# Z05_C8V_01.net
KiCad netlist of a schematic drawn in EAGLE
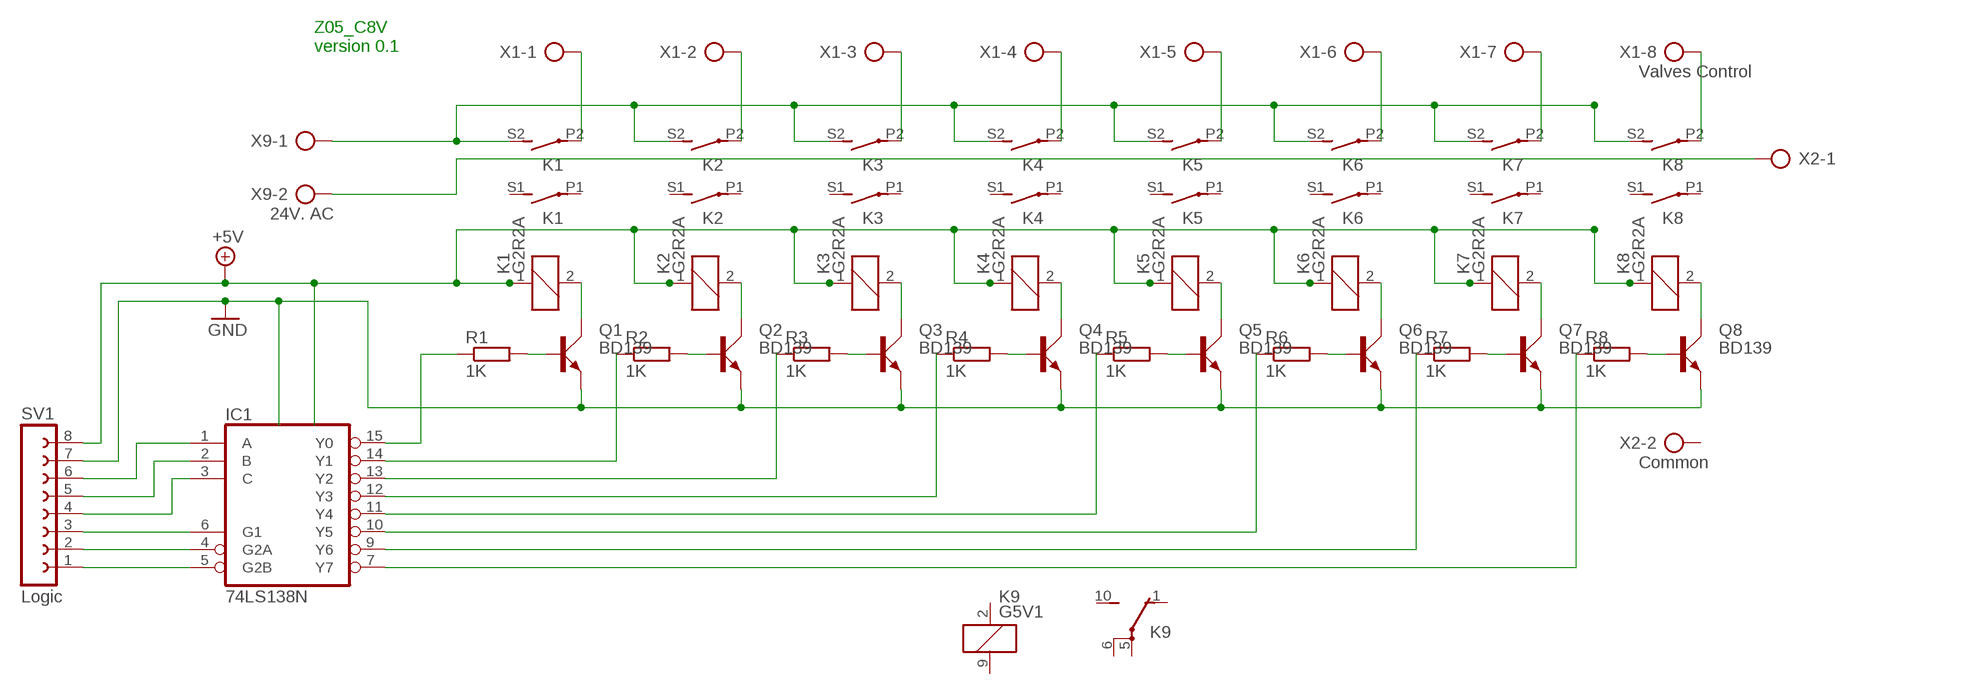
[diagram p0: schematic, sheet 1]

(export (version "E")
  (design (tool "Eeschema 10.0.6"))
  (components
    (comp (ref "IC1")
      (value "74LS138N")
      (footprint "eagle-import:DIL16")
      (libsource (lib "eagle-import") (part "74138NLS"))
    )
    (comp (ref "K1")
      (value "G2R2A")
      (footprint "eagle-import:G2R2A")
      (fields (field (name "MPN") "G2R-2A-DC24"))
      (libsource (lib "eagle-import") (part "G2R2A"))
    )
    (comp (ref "K2")
      (value "G2R2A")
      (footprint "eagle-import:G2R2A")
      (fields (field (name "MPN") "G2R-2A-DC24"))
      (libsource (lib "eagle-import") (part "G2R2A"))
    )
    (comp (ref "K3")
      (value "G2R2A")
      (footprint "eagle-import:G2R2A")
      (fields (field (name "MPN") "G2R-2A-DC24"))
      (libsource (lib "eagle-import") (part "G2R2A"))
    )
    (comp (ref "K4")
      (value "G2R2A")
      (footprint "eagle-import:G2R2A")
      (fields (field (name "MPN") "G2R-2A-DC24"))
      (libsource (lib "eagle-import") (part "G2R2A"))
    )
    (comp (ref "K5")
      (value "G2R2A")
      (footprint "eagle-import:G2R2A")
      (fields (field (name "MPN") "G2R-2A-DC24"))
      (libsource (lib "eagle-import") (part "G2R2A"))
    )
    (comp (ref "K6")
      (value "G2R2A")
      (footprint "eagle-import:G2R2A")
      (fields (field (name "MPN") "G2R-2A-DC24"))
      (libsource (lib "eagle-import") (part "G2R2A"))
    )
    (comp (ref "K7")
      (value "G2R2A")
      (footprint "eagle-import:G2R2A")
      (fields (field (name "MPN") "G2R-2A-DC24"))
      (libsource (lib "eagle-import") (part "G2R2A"))
    )
    (comp (ref "K8")
      (value "G2R2A")
      (footprint "eagle-import:G2R2A")
      (fields (field (name "MPN") "G2R-2A-DC24"))
      (libsource (lib "eagle-import") (part "G2R2A"))
    )
    (comp (ref "K9")
      (value "G5V1")
      (footprint "eagle-import:G5V1")
      (fields (field (name "MPN") "G5V-1-DC24"))
      (libsource (lib "eagle-import") (part "G5V1"))
    )
    (comp (ref "Q1")
      (value "BD139")
      (footprint "eagle-import:TO126AV")
      (libsource (lib "eagle-import") (part "BD139"))
    )
    (comp (ref "Q2")
      (value "BD139")
      (footprint "eagle-import:TO126AV")
      (libsource (lib "eagle-import") (part "BD139"))
    )
    (comp (ref "Q3")
      (value "BD139")
      (footprint "eagle-import:TO126AV")
      (libsource (lib "eagle-import") (part "BD139"))
    )
    (comp (ref "Q4")
      (value "BD139")
      (footprint "eagle-import:TO126AV")
      (libsource (lib "eagle-import") (part "BD139"))
    )
    (comp (ref "Q5")
      (value "BD139")
      (footprint "eagle-import:TO126AV")
      (libsource (lib "eagle-import") (part "BD139"))
    )
    (comp (ref "Q6")
      (value "BD139")
      (footprint "eagle-import:TO126AV")
      (libsource (lib "eagle-import") (part "BD139"))
    )
    (comp (ref "Q7")
      (value "BD139")
      (footprint "eagle-import:TO126AV")
      (libsource (lib "eagle-import") (part "BD139"))
    )
    (comp (ref "Q8")
      (value "BD139")
      (footprint "eagle-import:TO126AV")
      (libsource (lib "eagle-import") (part "BD139"))
    )
    (comp (ref "R1")
      (value "1K")
      (footprint "eagle-import:0204_7")
      (libsource (lib "eagle-import") (part "R-EU_0204/7"))
    )
    (comp (ref "R2")
      (value "1K")
      (footprint "eagle-import:0204_7")
      (libsource (lib "eagle-import") (part "R-EU_0204/7"))
    )
    (comp (ref "R3")
      (value "1K")
      (footprint "eagle-import:0204_7")
      (libsource (lib "eagle-import") (part "R-EU_0204/7"))
    )
    (comp (ref "R4")
      (value "1K")
      (footprint "eagle-import:0204_7")
      (libsource (lib "eagle-import") (part "R-EU_0204/7"))
    )
    (comp (ref "R5")
      (value "1K")
      (footprint "eagle-import:0204_7")
      (libsource (lib "eagle-import") (part "R-EU_0204/7"))
    )
    (comp (ref "R6")
      (value "1K")
      (footprint "eagle-import:0204_7")
      (libsource (lib "eagle-import") (part "R-EU_0204/7"))
    )
    (comp (ref "R7")
      (value "1K")
      (footprint "eagle-import:0204_7")
      (libsource (lib "eagle-import") (part "R-EU_0204/7"))
    )
    (comp (ref "R8")
      (value "1K")
      (footprint "eagle-import:0204_7")
      (libsource (lib "eagle-import") (part "R-EU_0204/7"))
    )
    (comp (ref "SV1")
      (value "Logic")
      (footprint "eagle-import:FE08")
      (libsource (lib "eagle-import") (part "FE08-1"))
    )
    (comp (ref "X1")
      (value "Valves Control")
      (footprint "eagle-import:AK300_8")
      (libsource (lib "eagle-import") (part "AK300/8"))
    )
    (comp (ref "X2")
      (value "Common")
      (footprint "eagle-import:AK300_2")
      (libsource (lib "eagle-import") (part "AK300/2"))
    )
    (comp (ref "X9")
      (value "24V. AC")
      (footprint "eagle-import:AK300_2")
      (libsource (lib "eagle-import") (part "AK300/2"))
    )
  )
  (nets
    (net (code "1") (name "+5V") (class "Default")
      (node (ref "K1") (pin "1") (pinfunction "1_1") (pintype "passive"))
      (node (ref "K2") (pin "1") (pinfunction "1_1") (pintype "passive"))
      (node (ref "K3") (pin "1") (pinfunction "1_1") (pintype "passive"))
      (node (ref "K4") (pin "1") (pinfunction "1_1") (pintype "passive"))
      (node (ref "K5") (pin "1") (pinfunction "1_1") (pintype "passive"))
      (node (ref "K6") (pin "1") (pinfunction "1_1") (pintype "passive"))
      (node (ref "K7") (pin "1") (pinfunction "1_1") (pintype "passive"))
      (node (ref "K8") (pin "1") (pinfunction "1_1") (pintype "passive"))
      (node (ref "SV1") (pin "8") (pinfunction "8_8") (pintype "passive"))
    )
    (net (code "2") (name "GND") (class "Default")
      (node (ref "Q1") (pin "E") (pinfunction "E_E") (pintype "passive"))
      (node (ref "Q2") (pin "E") (pinfunction "E_E") (pintype "passive"))
      (node (ref "Q3") (pin "E") (pinfunction "E_E") (pintype "passive"))
      (node (ref "Q4") (pin "E") (pinfunction "E_E") (pintype "passive"))
      (node (ref "Q5") (pin "E") (pinfunction "E_E") (pintype "passive"))
      (node (ref "Q6") (pin "E") (pinfunction "E_E") (pintype "passive"))
      (node (ref "Q7") (pin "E") (pinfunction "E_E") (pintype "passive"))
      (node (ref "Q8") (pin "E") (pinfunction "E_E") (pintype "passive"))
      (node (ref "SV1") (pin "7") (pinfunction "7_7") (pintype "passive"))
    )
    (net (code "3") (name "Net-(IC1A-A)") (class "Default")
      (node (ref "IC1") (pin "1") (pinfunction "A_1") (pintype "input"))
      (node (ref "SV1") (pin "6") (pinfunction "6_6") (pintype "passive"))
    )
    (net (code "4") (name "Net-(IC1A-B)") (class "Default")
      (node (ref "IC1") (pin "2") (pinfunction "B_2") (pintype "input"))
      (node (ref "SV1") (pin "5") (pinfunction "5_5") (pintype "passive"))
    )
    (net (code "5") (name "Net-(IC1A-C)") (class "Default")
      (node (ref "IC1") (pin "3") (pinfunction "C_3") (pintype "input"))
      (node (ref "SV1") (pin "4") (pinfunction "4_4") (pintype "passive"))
    )
    (net (code "6") (name "Net-(IC1A-G1)") (class "Default")
      (node (ref "IC1") (pin "6") (pinfunction "G1_6") (pintype "input"))
      (node (ref "SV1") (pin "3") (pinfunction "3_3") (pintype "passive"))
    )
    (net (code "7") (name "Net-(IC1A-G2A)") (class "Default")
      (node (ref "IC1") (pin "4") (pinfunction "G2A_4") (pintype "input"))
      (node (ref "SV1") (pin "2") (pinfunction "2_2") (pintype "passive"))
    )
    (net (code "8") (name "Net-(IC1A-G2B)") (class "Default")
      (node (ref "IC1") (pin "5") (pinfunction "G2B_5") (pintype "input"))
      (node (ref "SV1") (pin "1") (pinfunction "1_1") (pintype "passive"))
    )
    (net (code "9") (name "Net-(IC1A-Y0)") (class "Default")
      (node (ref "IC1") (pin "15") (pinfunction "Y0_15") (pintype "output"))
      (node (ref "R1") (pin "1") (pinfunction "1_1") (pintype "passive"))
    )
    (net (code "10") (name "Net-(IC1A-Y1)") (class "Default")
      (node (ref "IC1") (pin "14") (pinfunction "Y1_14") (pintype "output"))
      (node (ref "R2") (pin "1") (pinfunction "1_1") (pintype "passive"))
    )
    (net (code "11") (name "Net-(IC1A-Y2)") (class "Default")
      (node (ref "IC1") (pin "13") (pinfunction "Y2_13") (pintype "output"))
      (node (ref "R3") (pin "1") (pinfunction "1_1") (pintype "passive"))
    )
    (net (code "12") (name "Net-(IC1A-Y3)") (class "Default")
      (node (ref "IC1") (pin "12") (pinfunction "Y3_12") (pintype "output"))
      (node (ref "R4") (pin "1") (pinfunction "1_1") (pintype "passive"))
    )
    (net (code "13") (name "Net-(IC1A-Y4)") (class "Default")
      (node (ref "IC1") (pin "11") (pinfunction "Y4_11") (pintype "output"))
      (node (ref "R5") (pin "1") (pinfunction "1_1") (pintype "passive"))
    )
    (net (code "14") (name "Net-(IC1A-Y5)") (class "Default")
      (node (ref "IC1") (pin "10") (pinfunction "Y5_10") (pintype "output"))
      (node (ref "R6") (pin "1") (pinfunction "1_1") (pintype "passive"))
    )
    (net (code "15") (name "Net-(IC1A-Y6)") (class "Default")
      (node (ref "IC1") (pin "9") (pinfunction "Y6_9") (pintype "output"))
      (node (ref "R7") (pin "1") (pinfunction "1_1") (pintype "passive"))
    )
    (net (code "16") (name "Net-(IC1A-Y7)") (class "Default")
      (node (ref "IC1") (pin "7") (pinfunction "Y7_7") (pintype "output"))
      (node (ref "R8") (pin "1") (pinfunction "1_1") (pintype "passive"))
    )
    (net (code "17") (name "Net-(K1-Pad2)") (class "Default")
      (node (ref "K1") (pin "2") (pinfunction "2_2") (pintype "passive"))
      (node (ref "Q1") (pin "C") (pinfunction "C_C") (pintype "passive"))
    )
    (net (code "18") (name "Net-(K1C-P)") (class "Default")
      (node (ref "K1") (pin "P2") (pinfunction "P_P2") (pintype "passive"))
      (node (ref "X1") (pin "1") (pinfunction "KL_1") (pintype "passive"))
    )
    (net (code "19") (name "Net-(K1C-S)") (class "Default")
      (node (ref "K1") (pin "S2") (pinfunction "S_S2") (pintype "passive"))
      (node (ref "K2") (pin "S2") (pinfunction "S_S2") (pintype "passive"))
      (node (ref "K3") (pin "S2") (pinfunction "S_S2") (pintype "passive"))
      (node (ref "K4") (pin "S2") (pinfunction "S_S2") (pintype "passive"))
      (node (ref "K5") (pin "S2") (pinfunction "S_S2") (pintype "passive"))
      (node (ref "K6") (pin "S2") (pinfunction "S_S2") (pintype "passive"))
      (node (ref "K7") (pin "S2") (pinfunction "S_S2") (pintype "passive"))
      (node (ref "K8") (pin "S2") (pinfunction "S_S2") (pintype "passive"))
      (node (ref "X9") (pin "1") (pinfunction "KL_1") (pintype "passive"))
    )
    (net (code "20") (name "Net-(K2-Pad2)") (class "Default")
      (node (ref "K2") (pin "2") (pinfunction "2_2") (pintype "passive"))
      (node (ref "Q2") (pin "C") (pinfunction "C_C") (pintype "passive"))
    )
    (net (code "21") (name "Net-(K2C-P)") (class "Default")
      (node (ref "K2") (pin "P2") (pinfunction "P_P2") (pintype "passive"))
      (node (ref "X1") (pin "2") (pinfunction "KL_2") (pintype "passive"))
    )
    (net (code "22") (name "Net-(K3-Pad2)") (class "Default")
      (node (ref "K3") (pin "2") (pinfunction "2_2") (pintype "passive"))
      (node (ref "Q3") (pin "C") (pinfunction "C_C") (pintype "passive"))
    )
    (net (code "23") (name "Net-(K3C-P)") (class "Default")
      (node (ref "K3") (pin "P2") (pinfunction "P_P2") (pintype "passive"))
      (node (ref "X1") (pin "3") (pinfunction "KL_3") (pintype "passive"))
    )
    (net (code "24") (name "Net-(K4-Pad2)") (class "Default")
      (node (ref "K4") (pin "2") (pinfunction "2_2") (pintype "passive"))
      (node (ref "Q4") (pin "C") (pinfunction "C_C") (pintype "passive"))
    )
    (net (code "25") (name "Net-(K4C-P)") (class "Default")
      (node (ref "K4") (pin "P2") (pinfunction "P_P2") (pintype "passive"))
      (node (ref "X1") (pin "4") (pinfunction "KL_4") (pintype "passive"))
    )
    (net (code "26") (name "Net-(K5-Pad2)") (class "Default")
      (node (ref "K5") (pin "2") (pinfunction "2_2") (pintype "passive"))
      (node (ref "Q5") (pin "C") (pinfunction "C_C") (pintype "passive"))
    )
    (net (code "27") (name "Net-(K5C-P)") (class "Default")
      (node (ref "K5") (pin "P2") (pinfunction "P_P2") (pintype "passive"))
      (node (ref "X1") (pin "5") (pinfunction "KL_5") (pintype "passive"))
    )
    (net (code "28") (name "Net-(K6-Pad2)") (class "Default")
      (node (ref "K6") (pin "2") (pinfunction "2_2") (pintype "passive"))
      (node (ref "Q6") (pin "C") (pinfunction "C_C") (pintype "passive"))
    )
    (net (code "29") (name "Net-(K6C-P)") (class "Default")
      (node (ref "K6") (pin "P2") (pinfunction "P_P2") (pintype "passive"))
      (node (ref "X1") (pin "6") (pinfunction "KL_6") (pintype "passive"))
    )
    (net (code "30") (name "Net-(K7-Pad2)") (class "Default")
      (node (ref "K7") (pin "2") (pinfunction "2_2") (pintype "passive"))
      (node (ref "Q7") (pin "C") (pinfunction "C_C") (pintype "passive"))
    )
    (net (code "31") (name "Net-(K7C-P)") (class "Default")
      (node (ref "K7") (pin "P2") (pinfunction "P_P2") (pintype "passive"))
      (node (ref "X1") (pin "7") (pinfunction "KL_7") (pintype "passive"))
    )
    (net (code "32") (name "Net-(K8-Pad2)") (class "Default")
      (node (ref "K8") (pin "2") (pinfunction "2_2") (pintype "passive"))
      (node (ref "Q8") (pin "C") (pinfunction "C_C") (pintype "passive"))
    )
    (net (code "33") (name "Net-(K8C-P)") (class "Default")
      (node (ref "K8") (pin "P2") (pinfunction "P_P2") (pintype "passive"))
      (node (ref "X1") (pin "8") (pinfunction "KL_8") (pintype "passive"))
    )
    (net (code "34") (name "Net-(Q1-PadB)") (class "Default")
      (node (ref "Q1") (pin "B") (pinfunction "B_B") (pintype "passive"))
      (node (ref "R1") (pin "2") (pinfunction "2_2") (pintype "passive"))
    )
    (net (code "35") (name "Net-(Q2-PadB)") (class "Default")
      (node (ref "Q2") (pin "B") (pinfunction "B_B") (pintype "passive"))
      (node (ref "R2") (pin "2") (pinfunction "2_2") (pintype "passive"))
    )
    (net (code "36") (name "Net-(Q3-PadB)") (class "Default")
      (node (ref "Q3") (pin "B") (pinfunction "B_B") (pintype "passive"))
      (node (ref "R3") (pin "2") (pinfunction "2_2") (pintype "passive"))
    )
    (net (code "37") (name "Net-(Q4-PadB)") (class "Default")
      (node (ref "Q4") (pin "B") (pinfunction "B_B") (pintype "passive"))
      (node (ref "R4") (pin "2") (pinfunction "2_2") (pintype "passive"))
    )
    (net (code "38") (name "Net-(Q5-PadB)") (class "Default")
      (node (ref "Q5") (pin "B") (pinfunction "B_B") (pintype "passive"))
      (node (ref "R5") (pin "2") (pinfunction "2_2") (pintype "passive"))
    )
    (net (code "39") (name "Net-(Q6-PadB)") (class "Default")
      (node (ref "Q6") (pin "B") (pinfunction "B_B") (pintype "passive"))
      (node (ref "R6") (pin "2") (pinfunction "2_2") (pintype "passive"))
    )
    (net (code "40") (name "Net-(Q7-PadB)") (class "Default")
      (node (ref "Q7") (pin "B") (pinfunction "B_B") (pintype "passive"))
      (node (ref "R7") (pin "2") (pinfunction "2_2") (pintype "passive"))
    )
    (net (code "41") (name "Net-(Q8-PadB)") (class "Default")
      (node (ref "Q8") (pin "B") (pinfunction "B_B") (pintype "passive"))
      (node (ref "R8") (pin "2") (pinfunction "2_2") (pintype "passive"))
    )
    (net (code "42") (name "Net-(X2A-KL)") (class "Default")
      (node (ref "X2") (pin "1") (pinfunction "KL_1") (pintype "passive"))
      (node (ref "X9") (pin "2") (pinfunction "KL_2") (pintype "passive"))
    )
    (net (code "43") (name "unconnected-(K1B-P-PadP1)") (class "Default")
      (node (ref "K1") (pin "P1") (pinfunction "P_P1") (pintype "passive"))
    )
    (net (code "44") (name "unconnected-(K1B-S-PadS1)") (class "Default")
      (node (ref "K1") (pin "S1") (pinfunction "S_S1") (pintype "passive"))
    )
    (net (code "45") (name "unconnected-(K2B-P-PadP1)") (class "Default")
      (node (ref "K2") (pin "P1") (pinfunction "P_P1") (pintype "passive"))
    )
    (net (code "46") (name "unconnected-(K2B-S-PadS1)") (class "Default")
      (node (ref "K2") (pin "S1") (pinfunction "S_S1") (pintype "passive"))
    )
    (net (code "47") (name "unconnected-(K3B-P-PadP1)") (class "Default")
      (node (ref "K3") (pin "P1") (pinfunction "P_P1") (pintype "passive"))
    )
    (net (code "48") (name "unconnected-(K3B-S-PadS1)") (class "Default")
      (node (ref "K3") (pin "S1") (pinfunction "S_S1") (pintype "passive"))
    )
    (net (code "49") (name "unconnected-(K4B-P-PadP1)") (class "Default")
      (node (ref "K4") (pin "P1") (pinfunction "P_P1") (pintype "passive"))
    )
    (net (code "50") (name "unconnected-(K4B-S-PadS1)") (class "Default")
      (node (ref "K4") (pin "S1") (pinfunction "S_S1") (pintype "passive"))
    )
    (net (code "51") (name "unconnected-(K5B-P-PadP1)") (class "Default")
      (node (ref "K5") (pin "P1") (pinfunction "P_P1") (pintype "passive"))
    )
    (net (code "52") (name "unconnected-(K5B-S-PadS1)") (class "Default")
      (node (ref "K5") (pin "S1") (pinfunction "S_S1") (pintype "passive"))
    )
    (net (code "53") (name "unconnected-(K6B-P-PadP1)") (class "Default")
      (node (ref "K6") (pin "P1") (pinfunction "P_P1") (pintype "passive"))
    )
    (net (code "54") (name "unconnected-(K6B-S-PadS1)") (class "Default")
      (node (ref "K6") (pin "S1") (pinfunction "S_S1") (pintype "passive"))
    )
    (net (code "55") (name "unconnected-(K7B-P-PadP1)") (class "Default")
      (node (ref "K7") (pin "P1") (pinfunction "P_P1") (pintype "passive"))
    )
    (net (code "56") (name "unconnected-(K7B-S-PadS1)") (class "Default")
      (node (ref "K7") (pin "S1") (pinfunction "S_S1") (pintype "passive"))
    )
    (net (code "57") (name "unconnected-(K8B-P-PadP1)") (class "Default")
      (node (ref "K8") (pin "P1") (pinfunction "P_P1") (pintype "passive"))
    )
    (net (code "58") (name "unconnected-(K8B-S-PadS1)") (class "Default")
      (node (ref "K8") (pin "S1") (pinfunction "S_S1") (pintype "passive"))
    )
    (net (code "59") (name "unconnected-(K9A-1-Pad2)") (class "Default")
      (node (ref "K9") (pin "2") (pinfunction "1_2") (pintype "passive"))
    )
    (net (code "60") (name "unconnected-(K9A-2-Pad9)") (class "Default")
      (node (ref "K9") (pin "9") (pinfunction "2_9") (pintype "passive"))
    )
    (net (code "61") (name "unconnected-(K9B-O-Pad1)") (class "Default")
      (node (ref "K9") (pin "1") (pinfunction "O_1") (pintype "passive"))
    )
    (net (code "62") (name "unconnected-(K9B-P-Pad5)") (class "Default")
      (node (ref "K9") (pin "5") (pinfunction "P_5") (pintype "passive"))
    )
    (net (code "63") (name "unconnected-(K9B-P-Pad6)") (class "Default")
      (node (ref "K9") (pin "6") (pinfunction "P_6") (pintype "passive"))
    )
    (net (code "64") (name "unconnected-(K9B-S-Pad10)") (class "Default")
      (node (ref "K9") (pin "10") (pinfunction "S_10") (pintype "passive"))
    )
    (net (code "65") (name "unconnected-(X2B-KL-Pad2)") (class "Default")
      (node (ref "X2") (pin "2") (pinfunction "KL_2") (pintype "passive"))
    )
  )
)
